# Display.net
KiCad netlist of a schematic drawn in Altium Designer
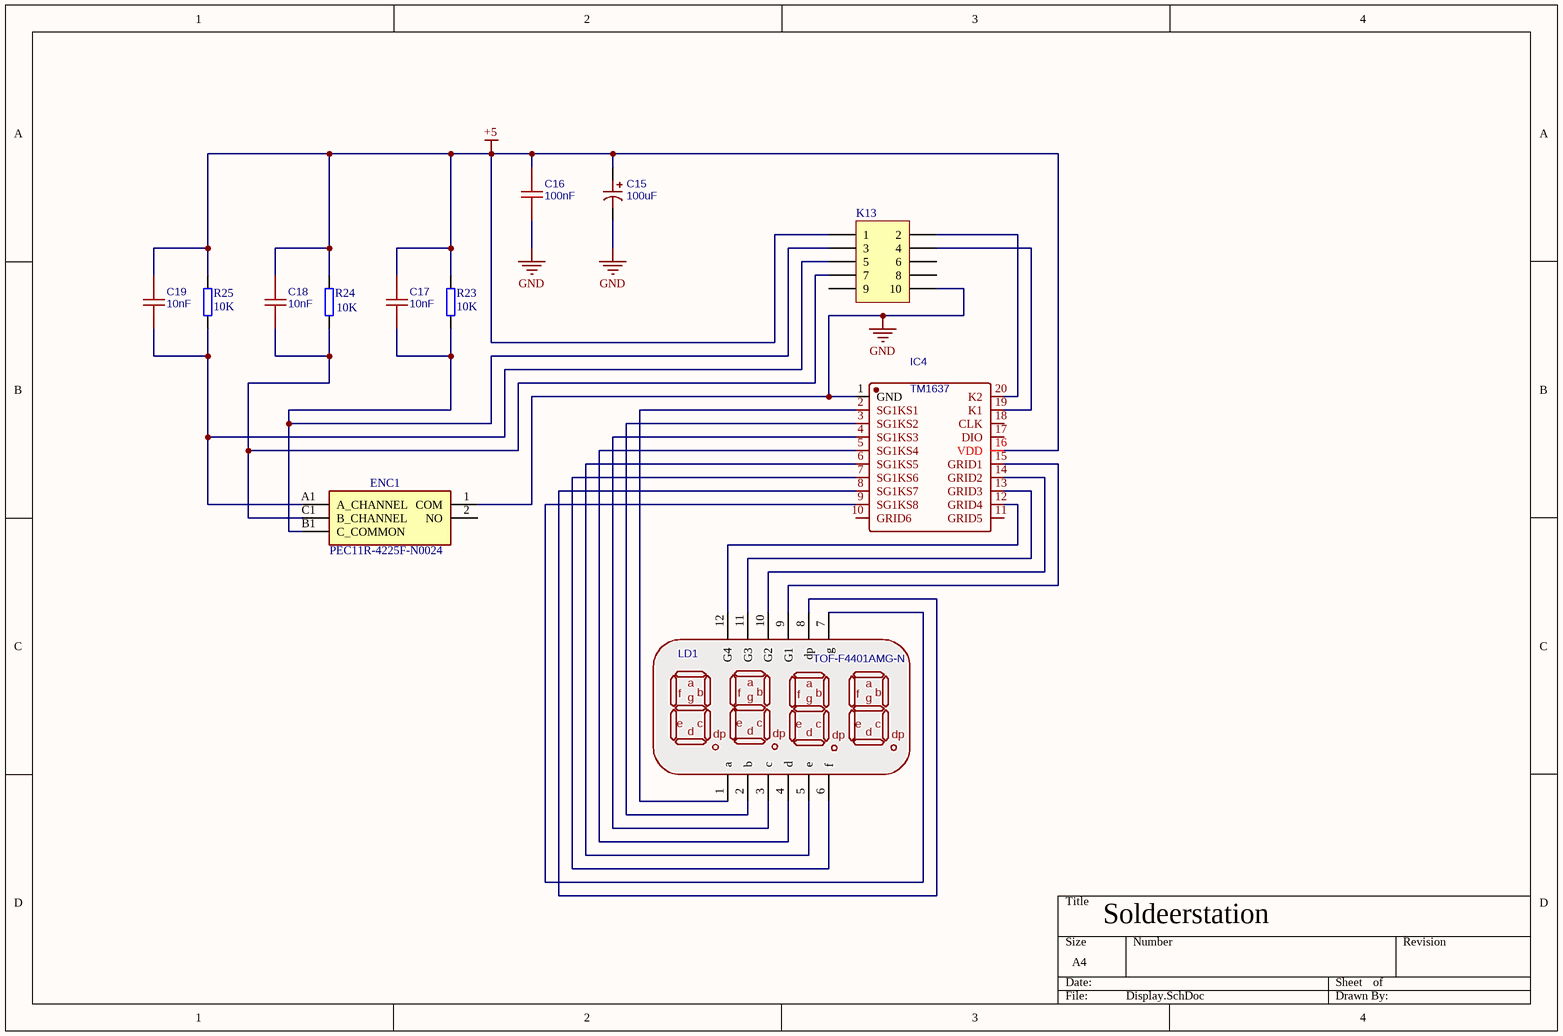
[diagram p0: Display.SchDoc]

(export (version "E")
  (design (tool "Eeschema 10.0.6"))
  (components
    (comp (ref "C15")
      (value "100uF")
      (footprint "C4 100uF")
      (fields
        (field (name "BOM_SUPPLIER PART") "C445063")
        (field (name "BOM_MANUFACTURER PART") "UWT1H101MNL1GS")
        (field (name "CONTRIBUTOR") "LCSC")
      )
      (libsource (lib "SoldeerStation") (part "C4 100uF"))
    )
    (comp (ref "C16")
      (value "100nF")
      (footprint "C6,7,12,13 10nF")
      (fields
        (field (name "BOM_SUPPLIER PART") "C376921")
        (field (name "BOM_MANUFACTURER PART") "TCC0805X7R103M500DT")
        (field (name "CONTRIBUTOR") "LCSC")
      )
      (libsource (lib "SoldeerStation") (part "C6,7,12,13 10nF"))
    )
    (comp (ref "C17")
      (value "10nF")
      (footprint "C6,7,12,13 10nF")
      (fields
        (field (name "BOM_SUPPLIER PART") "C376921")
        (field (name "BOM_MANUFACTURER PART") "TCC0805X7R103M500DT")
        (field (name "CONTRIBUTOR") "LCSC")
      )
      (libsource (lib "SoldeerStation") (part "C6,7,12,13 10nF"))
    )
    (comp (ref "C18")
      (value "10nF")
      (footprint "C6,7,12,13 10nF")
      (fields
        (field (name "BOM_SUPPLIER PART") "C376921")
        (field (name "BOM_MANUFACTURER PART") "TCC0805X7R103M500DT")
        (field (name "CONTRIBUTOR") "LCSC")
      )
      (libsource (lib "SoldeerStation") (part "C6,7,12,13 10nF"))
    )
    (comp (ref "C19")
      (value "10nF")
      (footprint "C6,7,12,13 10nF")
      (fields
        (field (name "BOM_SUPPLIER PART") "C376921")
        (field (name "BOM_MANUFACTURER PART") "TCC0805X7R103M500DT")
        (field (name "CONTRIBUTOR") "LCSC")
      )
      (libsource (lib "SoldeerStation") (part "C6,7,12,13 10nF"))
    )
    (comp (ref "ENC1")
      (value "PEC11R-4225F-N0024")
      (footprint "ENC1 draai encoder")
      (fields (field (name "MOUSER PART NUMBER") "652-PEC11R-4225F-N24"))
      (libsource (lib "SoldeerStation") (part "ENC1 Draai encoder"))
    )
    (comp (ref "IC4")
      (value "TM1637")
      (footprint "IC4 Led driver")
      (description "TM1637(TA2007)")
      (fields (field (name "BOM_SUPPLIER PART") "C5337160") (field (name "CONTRIBUTOR") "lcsc"))
      (libsource (lib "SoldeerStation") (part "IC4 Led driver"))
    )
    (comp (ref "K13")
      (value "~")
      (footprint "HDR2X5")
      (description "Header, 5-Pin, Dual row")
      (fields (field (name "PUBLISHER") "Altium Limited"))
      (libsource (lib "Miscellaneous Connectors") (part "Header 5X2"))
    )
    (comp (ref "LD1")
      (value "TOF-F4401AMG-N")
      (footprint "LED1")
      (fields (field (name "BOM_SUPPLIER PART") "C325426") (field (name "CONTRIBUTOR") "LCSC"))
      (libsource (lib "SoldeerStation") (part "LED1"))
    )
    (comp (ref "R23")
      (value "10K")
      (footprint "RESC2013X50X30ML20T20")
      (fields (field (name "MANUFACTURER") "Vishay Dale") (field (name "PART NUMBER") "CRCW08050000Z0EA"))
      (libsource (lib "SoldeerStation") (part "R Resistor"))
    )
    (comp (ref "R24")
      (value "10K")
      (footprint "RESC2013X50X30ML20T20")
      (fields (field (name "MANUFACTURER") "Vishay Dale") (field (name "PART NUMBER") "CRCW08050000Z0EA"))
      (libsource (lib "SoldeerStation") (part "R Resistor"))
    )
    (comp (ref "R25")
      (value "10K")
      (footprint "RESC2013X50X30ML20T20")
      (fields (field (name "MANUFACTURER") "Vishay Dale") (field (name "PART NUMBER") "CRCW08050000Z0EA"))
      (libsource (lib "SoldeerStation") (part "R Resistor"))
    )
  )
  (nets
    (net (code "1") (name "+5") (class "Default")
      (node (ref "C15") (pin "1") (pinfunction "1_1") (pintype "passive"))
      (node (ref "C16") (pin "2") (pinfunction "2_2") (pintype "passive"))
      (node (ref "C17") (pin "2") (pinfunction "2_2") (pintype "passive"))
      (node (ref "C18") (pin "2") (pinfunction "2_2") (pintype "passive"))
      (node (ref "C19") (pin "2") (pinfunction "2_2") (pintype "passive"))
      (node (ref "IC4") (pin "16") (pinfunction "VDD_16") (pintype "passive"))
      (node (ref "K13") (pin "1") (pinfunction "1_1") (pintype "passive"))
      (node (ref "R23") (pin "2") (pinfunction "2_2") (pintype "passive"))
      (node (ref "R24") (pin "2") (pinfunction "2_2") (pintype "passive"))
      (node (ref "R25") (pin "2") (pinfunction "2_2") (pintype "passive"))
    )
    (net (code "2") (name "GND") (class "Default")
      (node (ref "C15") (pin "2") (pinfunction "2_2") (pintype "passive"))
      (node (ref "C16") (pin "1") (pinfunction "1_1") (pintype "passive"))
      (node (ref "ENC1") (pin "1") (pinfunction "COM_1") (pintype "passive"))
      (node (ref "IC4") (pin "1") (pinfunction "GND_1") (pintype "passive"))
      (node (ref "K13") (pin "10") (pinfunction "10_10") (pintype "passive"))
    )
    (net (code "3") (name "Net-(ENC1-A_CHANNEL)") (class "Default")
      (node (ref "C19") (pin "1") (pinfunction "1_1") (pintype "passive"))
      (node (ref "ENC1") (pin "A1") (pinfunction "A_CHANNEL_A1") (pintype "passive"))
      (node (ref "K13") (pin "5") (pinfunction "5_5") (pintype "passive"))
      (node (ref "R25") (pin "1") (pinfunction "1_1") (pintype "passive"))
    )
    (net (code "4") (name "Net-(ENC1-B_CHANNEL)") (class "Default")
      (node (ref "C18") (pin "1") (pinfunction "1_1") (pintype "passive"))
      (node (ref "ENC1") (pin "C1") (pinfunction "B_CHANNEL_C1") (pintype "passive"))
      (node (ref "K13") (pin "7") (pinfunction "7_7") (pintype "passive"))
      (node (ref "R24") (pin "1") (pinfunction "1_1") (pintype "passive"))
    )
    (net (code "5") (name "Net-(ENC1-C_COMMON)") (class "Default")
      (node (ref "C17") (pin "1") (pinfunction "1_1") (pintype "passive"))
      (node (ref "ENC1") (pin "B1") (pinfunction "C_COMMON_B1") (pintype "passive"))
      (node (ref "K13") (pin "3") (pinfunction "3_3") (pintype "passive"))
      (node (ref "R23") (pin "1") (pinfunction "1_1") (pintype "passive"))
    )
    (net (code "6") (name "Net-(IC4-GRID1)") (class "Default")
      (node (ref "IC4") (pin "15") (pinfunction "GRID1_15") (pintype "passive"))
      (node (ref "LD1") (pin "9") (pinfunction "G1_9") (pintype "passive"))
    )
    (net (code "7") (name "Net-(IC4-GRID2)") (class "Default")
      (node (ref "IC4") (pin "14") (pinfunction "GRID2_14") (pintype "passive"))
      (node (ref "LD1") (pin "10") (pinfunction "G2_10") (pintype "passive"))
    )
    (net (code "8") (name "Net-(IC4-GRID3)") (class "Default")
      (node (ref "IC4") (pin "13") (pinfunction "GRID3_13") (pintype "passive"))
      (node (ref "LD1") (pin "11") (pinfunction "G3_11") (pintype "passive"))
    )
    (net (code "9") (name "Net-(IC4-GRID4)") (class "Default")
      (node (ref "IC4") (pin "12") (pinfunction "GRID4_12") (pintype "passive"))
      (node (ref "LD1") (pin "12") (pinfunction "G4_12") (pintype "passive"))
    )
    (net (code "10") (name "Net-(IC4-K1)") (class "Default")
      (node (ref "IC4") (pin "19") (pinfunction "K1_19") (pintype "passive"))
      (node (ref "K13") (pin "4") (pinfunction "4_4") (pintype "passive"))
    )
    (net (code "11") (name "Net-(IC4-K2)") (class "Default")
      (node (ref "IC4") (pin "20") (pinfunction "K2_20") (pintype "passive"))
      (node (ref "K13") (pin "2") (pinfunction "2_2") (pintype "passive"))
    )
    (net (code "12") (name "Net-(IC4-SG1KS1)") (class "Default")
      (node (ref "IC4") (pin "2") (pinfunction "SG1KS1_2") (pintype "passive"))
      (node (ref "LD1") (pin "1") (pinfunction "a_1") (pintype "passive"))
    )
    (net (code "13") (name "Net-(IC4-SG1KS2)") (class "Default")
      (node (ref "IC4") (pin "3") (pinfunction "SG1KS2_3") (pintype "passive"))
      (node (ref "LD1") (pin "2") (pinfunction "b_2") (pintype "passive"))
    )
    (net (code "14") (name "Net-(IC4-SG1KS3)") (class "Default")
      (node (ref "IC4") (pin "4") (pinfunction "SG1KS3_4") (pintype "passive"))
      (node (ref "LD1") (pin "3") (pinfunction "c_3") (pintype "passive"))
    )
    (net (code "15") (name "Net-(IC4-SG1KS4)") (class "Default")
      (node (ref "IC4") (pin "5") (pinfunction "SG1KS4_5") (pintype "passive"))
      (node (ref "LD1") (pin "4") (pinfunction "d_4") (pintype "passive"))
    )
    (net (code "16") (name "Net-(IC4-SG1KS5)") (class "Default")
      (node (ref "IC4") (pin "6") (pinfunction "SG1KS5_6") (pintype "passive"))
      (node (ref "LD1") (pin "5") (pinfunction "e_5") (pintype "passive"))
    )
    (net (code "17") (name "Net-(IC4-SG1KS6)") (class "Default")
      (node (ref "IC4") (pin "7") (pinfunction "SG1KS6_7") (pintype "passive"))
      (node (ref "LD1") (pin "6") (pinfunction "f_6") (pintype "passive"))
    )
    (net (code "18") (name "Net-(IC4-SG1KS7)") (class "Default")
      (node (ref "IC4") (pin "8") (pinfunction "SG1KS7_8") (pintype "passive"))
      (node (ref "LD1") (pin "8") (pinfunction "dp_8") (pintype "passive"))
    )
    (net (code "19") (name "Net-(IC4-SG1KS8)") (class "Default")
      (node (ref "IC4") (pin "9") (pinfunction "SG1KS8_9") (pintype "passive"))
      (node (ref "LD1") (pin "7") (pinfunction "g_7") (pintype "passive"))
    )
    (net (code "20") (name "unconnected-(ENC1-NO-Pad2)") (class "Default")
      (node (ref "ENC1") (pin "2") (pinfunction "NO_2") (pintype "passive"))
    )
    (net (code "21") (name "unconnected-(IC4-CLK-Pad18)") (class "Default")
      (node (ref "IC4") (pin "18") (pinfunction "CLK_18") (pintype "passive"))
    )
    (net (code "22") (name "unconnected-(IC4-DIO-Pad17)") (class "Default")
      (node (ref "IC4") (pin "17") (pinfunction "DIO_17") (pintype "passive"))
    )
    (net (code "23") (name "unconnected-(IC4-GRID5-Pad11)") (class "Default")
      (node (ref "IC4") (pin "11") (pinfunction "GRID5_11") (pintype "passive"))
    )
    (net (code "24") (name "unconnected-(IC4-GRID6-Pad10)") (class "Default")
      (node (ref "IC4") (pin "10") (pinfunction "GRID6_10") (pintype "passive"))
    )
    (net (code "25") (name "unconnected-(K13-Pad6)") (class "Default")
      (node (ref "K13") (pin "6") (pinfunction "6_6") (pintype "passive"))
    )
    (net (code "26") (name "unconnected-(K13-Pad8)") (class "Default")
      (node (ref "K13") (pin "8") (pinfunction "8_8") (pintype "passive"))
    )
    (net (code "27") (name "unconnected-(K13-Pad9)") (class "Default")
      (node (ref "K13") (pin "9") (pinfunction "9_9") (pintype "passive"))
    )
  )
)
